# Xe_VDK_Schematic_-_Copy.net
KiCad netlist of a schematic drawn in Altium Designer
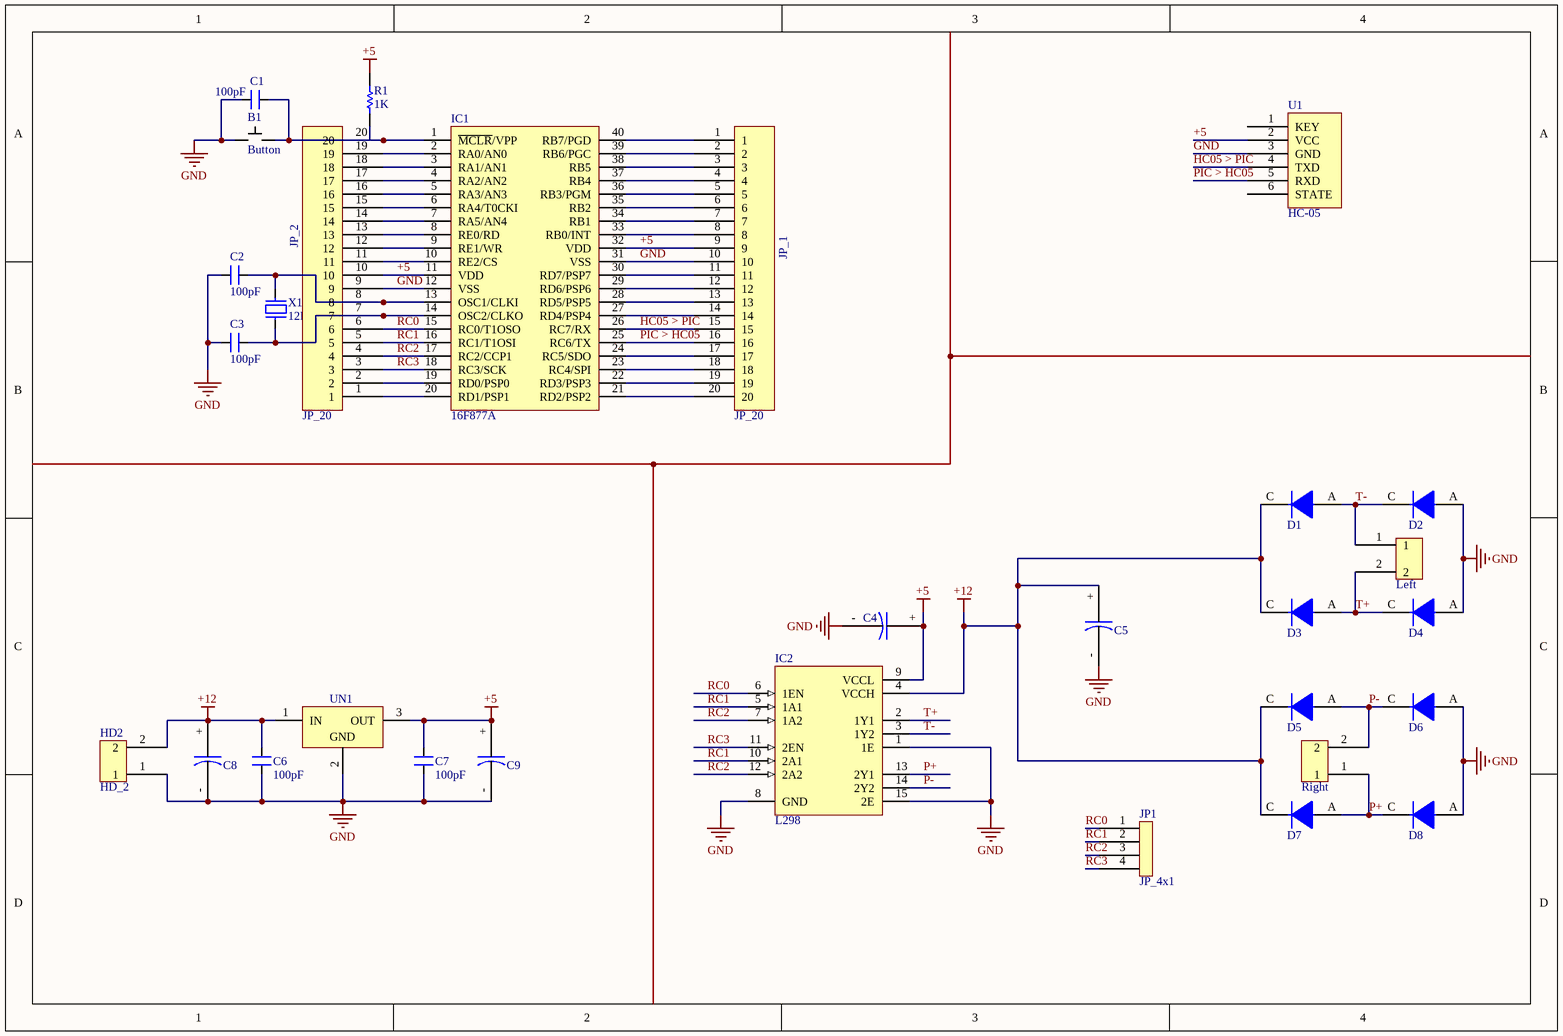
[diagram p0: Xe_VDK_Schematic - Copy.SchDoc]

(export (version "E")
  (design (tool "Eeschema 10.0.6"))
  (components
    (comp (ref "B1")
      (value "Button")
      (footprint "Button - 4-pin")
      (libsource (lib "LuongTanDat") (part "Button"))
    )
    (comp (ref "C1")
      (value "100pF")
      (footprint "CN1")
      (description "Cap np  1pF - 472pF")
      (libsource (lib "syhaunguyen") (part "CN1"))
    )
    (comp (ref "C2")
      (value "100pF")
      (footprint "CN1")
      (description "Cap np  1pF - 472pF")
      (libsource (lib "syhaunguyen") (part "CN1"))
    )
    (comp (ref "C3")
      (value "100pF")
      (footprint "CN1")
      (description "Cap np  1pF - 472pF")
      (libsource (lib "syhaunguyen") (part "CN1"))
    )
    (comp (ref "C4")
      (value "Pol-Cap")
      (footprint "Pol_200mil")
      (description "Tụ điện phân cực")
      (libsource (lib "LuongTanDat") (part "Pol-Cap"))
    )
    (comp (ref "C5")
      (value "Pol-Cap")
      (footprint "Pol_200mil")
      (description "Tụ điện phân cực")
      (libsource (lib "LuongTanDat") (part "Pol-Cap"))
    )
    (comp (ref "C6")
      (value "100pF")
      (footprint "CN1")
      (description "Cap np  1pF - 472pF")
      (libsource (lib "syhaunguyen") (part "CN1"))
    )
    (comp (ref "C7")
      (value "100pF")
      (footprint "CN1")
      (description "Cap np  1pF - 472pF")
      (libsource (lib "syhaunguyen") (part "CN1"))
    )
    (comp (ref "C8")
      (value "Pol-Cap")
      (footprint "POL_250mil")
      (description "Tụ điện phân cực")
      (libsource (lib "LuongTanDat") (part "Pol-Cap"))
    )
    (comp (ref "C9")
      (value "Pol-Cap")
      (footprint "POL_250mil")
      (description "Tụ điện phân cực")
      (libsource (lib "LuongTanDat") (part "Pol-Cap"))
    )
    (comp (ref "D1") (value "Diode") (footprint "Diode") (libsource (lib "LuongTanDat") (part "Diode")))
    (comp (ref "D2") (value "Diode") (footprint "Diode") (libsource (lib "LuongTanDat") (part "Diode")))
    (comp (ref "D3") (value "Diode") (footprint "Diode") (libsource (lib "LuongTanDat") (part "Diode")))
    (comp (ref "D4") (value "Diode") (footprint "Diode") (libsource (lib "LuongTanDat") (part "Diode")))
    (comp (ref "D5") (value "Diode") (footprint "Diode") (libsource (lib "LuongTanDat") (part "Diode")))
    (comp (ref "D6") (value "Diode") (footprint "Diode") (libsource (lib "LuongTanDat") (part "Diode")))
    (comp (ref "D7") (value "Diode") (footprint "Diode") (libsource (lib "LuongTanDat") (part "Diode")))
    (comp (ref "D8") (value "Diode") (footprint "Diode") (libsource (lib "LuongTanDat") (part "Diode")))
    (comp (ref "HD2") (value "HD_2") (footprint "Header 2") (libsource (lib "LuongTanDat") (part "HD_2")))
    (comp (ref "IC1")
      (value "16F877A")
      (footprint "DIP40/W0.6")
      (description "8K FLASH, 368B RAM, 256B EFROM")
      (fields (field (name "COPYRIGHT BY") "VanDungEvn"))
      (libsource (lib "syhaunguyen") (part "16F877"))
    )
    (comp (ref "IC2")
      (value "L298")
      (footprint "DIP15SL2")
      (description "Dual Full-H Driver")
      (fields (field (name "PUBLISHER") "Altium Limited"))
      (libsource (lib "VioletofSun") (part "L298"))
    )
    (comp (ref "JP1") (value "JP_4x1") (footprint "JP_4x1") (libsource (lib "LuongTanDat") (part "JP_4x1")))
    (comp (ref "JP_1") (value "JP_20") (footprint "JP_20") (libsource (lib "LuongTanDat") (part "JP_20")))
    (comp (ref "JP_2") (value "JP_20") (footprint "JP_20") (libsource (lib "") (part "JP_20_1")))
    (comp (ref "Left") (value "HD_2") (footprint "Header 2") (libsource (lib "") (part "HD_2_1")))
    (comp (ref "R1")
      (value "1K")
      (footprint "RES 1/2W")
      (description "Resistor")
      (fields (field (name "Comment") "RESISTOR"))
      (libsource (lib "PIF_Library") (part "RESISTOR"))
    )
    (comp (ref "Right") (value "HD_2") (footprint "Header 2") (libsource (lib "LuongTanDat") (part "HD_2")))
    (comp (ref "U1") (value "HC-05") (footprint "HC-05") (libsource (lib "LuongTanDat") (part "HC-05")))
    (comp (ref "UN1")
      (value "LM7805")
      (footprint "QTO-220")
      (description "Positive Voltage Regulator")
      (libsource (lib "PIF_Library") (part "LM7805"))
    )
    (comp (ref "X1")
      (value "12Mhz")
      (footprint "XT2")
      (description "Crystal, 32.768 KHz, -40 to 85 degC, 3.2 x 1.5 x 0.9 mm SMD")
      (libsource (lib "ImetAltiumLibrary") (part "XT2"))
    )
  )
  (nets
    (net (code "1") (name "+5") (class "Default")
      (node (ref "C4") (pin "+") (pintype "passive"))
      (node (ref "C7") (pin "2") (pinfunction "2_2") (pintype "passive"))
      (node (ref "C9") (pin "+") (pintype "passive"))
      (node (ref "IC1") (pin "11") (pinfunction "VDD_11") (pintype "passive"))
      (node (ref "IC1") (pin "32") (pinfunction "VDD_32") (pintype "passive"))
      (node (ref "IC2") (pin "9") (pinfunction "VCCL_9") (pintype "power_in"))
      (node (ref "JP_1") (pin "9") (pinfunction "9_9") (pintype "passive"))
      (node (ref "JP_2") (pin "10") (pinfunction "10_10") (pintype "passive"))
      (node (ref "R1") (pin "2") (pinfunction "2_2") (pintype "passive"))
      (node (ref "U1") (pin "2") (pinfunction "VCC_2") (pintype "passive"))
      (node (ref "UN1") (pin "3") (pinfunction "OUT_3") (pintype "power_in"))
    )
    (net (code "2") (name "+12") (class "Default")
      (node (ref "C5") (pin "+") (pintype "passive"))
      (node (ref "C6") (pin "2") (pinfunction "2_2") (pintype "passive"))
      (node (ref "C8") (pin "+") (pintype "passive"))
      (node (ref "D1") (pin "C") (pinfunction "2_C") (pintype "passive"))
      (node (ref "D3") (pin "C") (pinfunction "2_C") (pintype "passive"))
      (node (ref "D5") (pin "C") (pinfunction "2_C") (pintype "passive"))
      (node (ref "D7") (pin "C") (pinfunction "2_C") (pintype "passive"))
      (node (ref "HD2") (pin "2") (pinfunction "2_2") (pintype "passive"))
      (node (ref "IC2") (pin "4") (pinfunction "VCCH_4") (pintype "power_in"))
      (node (ref "UN1") (pin "1") (pinfunction "IN_1") (pintype "power_in"))
    )
    (net (code "3") (name "/HC05 > PIC") (class "Default")
      (node (ref "IC1") (pin "26") (pinfunction "RC7/RX_26") (pintype "passive"))
      (node (ref "JP_1") (pin "15") (pinfunction "15_15") (pintype "passive"))
      (node (ref "U1") (pin "4") (pinfunction "TXD_4") (pintype "passive"))
    )
    (net (code "4") (name "/P+") (class "Default")
      (node (ref "D7") (pin "A") (pinfunction "1_A") (pintype "passive"))
      (node (ref "D8") (pin "C") (pinfunction "2_C") (pintype "passive"))
      (node (ref "IC2") (pin "13") (pinfunction "2Y1_13") (pintype "tri_state"))
      (node (ref "Right") (pin "1") (pinfunction "1_1") (pintype "passive"))
    )
    (net (code "5") (name "/P-") (class "Default")
      (node (ref "D5") (pin "A") (pinfunction "1_A") (pintype "passive"))
      (node (ref "D6") (pin "C") (pinfunction "2_C") (pintype "passive"))
      (node (ref "IC2") (pin "14") (pinfunction "2Y2_14") (pintype "tri_state"))
      (node (ref "Right") (pin "2") (pinfunction "2_2") (pintype "passive"))
    )
    (net (code "6") (name "/PIC > HC05") (class "Default")
      (node (ref "IC1") (pin "25") (pinfunction "RC6/TX_25") (pintype "passive"))
      (node (ref "JP_1") (pin "16") (pinfunction "16_16") (pintype "passive"))
      (node (ref "U1") (pin "5") (pinfunction "RXD_5") (pintype "passive"))
    )
    (net (code "7") (name "/RC0") (class "Default")
      (node (ref "IC1") (pin "15") (pinfunction "RC0/T1OSO_15") (pintype "passive"))
      (node (ref "IC2") (pin "6") (pinfunction "1EN_6") (pintype "input"))
      (node (ref "JP1") (pin "1") (pinfunction "1_1") (pintype "passive"))
      (node (ref "JP_2") (pin "6") (pinfunction "6_6") (pintype "passive"))
    )
    (net (code "8") (name "/RC1") (class "Default")
      (node (ref "IC1") (pin "16") (pinfunction "RC1/T1OSI_16") (pintype "passive"))
      (node (ref "IC2") (pin "10") (pinfunction "2A1_10") (pintype "input"))
      (node (ref "IC2") (pin "5") (pinfunction "1A1_5") (pintype "input"))
      (node (ref "JP1") (pin "2") (pinfunction "2_2") (pintype "passive"))
      (node (ref "JP_2") (pin "5") (pinfunction "5_5") (pintype "passive"))
    )
    (net (code "9") (name "/RC2") (class "Default")
      (node (ref "IC1") (pin "17") (pinfunction "RC2/CCP1_17") (pintype "passive"))
      (node (ref "IC2") (pin "12") (pinfunction "2A2_12") (pintype "input"))
      (node (ref "IC2") (pin "7") (pinfunction "1A2_7") (pintype "input"))
      (node (ref "JP1") (pin "3") (pinfunction "3_3") (pintype "passive"))
      (node (ref "JP_2") (pin "4") (pinfunction "4_4") (pintype "passive"))
    )
    (net (code "10") (name "/RC3") (class "Default")
      (node (ref "IC1") (pin "18") (pinfunction "RC3/SCK_18") (pintype "passive"))
      (node (ref "IC2") (pin "11") (pinfunction "2EN_11") (pintype "input"))
      (node (ref "JP1") (pin "4") (pinfunction "4_4") (pintype "passive"))
      (node (ref "JP_2") (pin "3") (pinfunction "3_3") (pintype "passive"))
    )
    (net (code "11") (name "/T+") (class "Default")
      (node (ref "D3") (pin "A") (pinfunction "1_A") (pintype "passive"))
      (node (ref "D4") (pin "C") (pinfunction "2_C") (pintype "passive"))
      (node (ref "IC2") (pin "2") (pinfunction "1Y1_2") (pintype "tri_state"))
      (node (ref "Left") (pin "2") (pinfunction "2_2") (pintype "passive"))
    )
    (net (code "12") (name "/T-") (class "Default")
      (node (ref "D1") (pin "A") (pinfunction "1_A") (pintype "passive"))
      (node (ref "D2") (pin "C") (pinfunction "2_C") (pintype "passive"))
      (node (ref "IC2") (pin "3") (pinfunction "1Y2_3") (pintype "tri_state"))
      (node (ref "Left") (pin "1") (pinfunction "1_1") (pintype "passive"))
    )
    (net (code "13") (name "GND") (class "Default")
      (node (ref "B1") (pin "1") (pinfunction "0_1") (pintype "passive"))
      (node (ref "C1") (pin "1") (pinfunction "1_1") (pintype "passive"))
      (node (ref "C2") (pin "1") (pinfunction "1_1") (pintype "passive"))
      (node (ref "C3") (pin "1") (pinfunction "1_1") (pintype "passive"))
      (node (ref "C4") (pin "-") (pintype "passive"))
      (node (ref "C5") (pin "-") (pintype "passive"))
      (node (ref "C6") (pin "1") (pinfunction "1_1") (pintype "passive"))
      (node (ref "C7") (pin "1") (pinfunction "1_1") (pintype "passive"))
      (node (ref "C8") (pin "-") (pintype "passive"))
      (node (ref "C9") (pin "-") (pintype "passive"))
      (node (ref "D2") (pin "A") (pinfunction "1_A") (pintype "passive"))
      (node (ref "D4") (pin "A") (pinfunction "1_A") (pintype "passive"))
      (node (ref "D6") (pin "A") (pinfunction "1_A") (pintype "passive"))
      (node (ref "D8") (pin "A") (pinfunction "1_A") (pintype "passive"))
      (node (ref "HD2") (pin "1") (pinfunction "1_1") (pintype "passive"))
      (node (ref "IC1") (pin "12") (pinfunction "VSS_12") (pintype "passive"))
      (node (ref "IC1") (pin "31") (pinfunction "VSS_31") (pintype "passive"))
      (node (ref "IC2") (pin "1") (pinfunction "1E_1") (pintype "passive"))
      (node (ref "IC2") (pin "15") (pinfunction "2E_15") (pintype "passive"))
      (node (ref "IC2") (pin "8") (pinfunction "GND_8") (pintype "power_in"))
      (node (ref "JP_1") (pin "10") (pinfunction "10_10") (pintype "passive"))
      (node (ref "JP_2") (pin "9") (pinfunction "9_9") (pintype "passive"))
      (node (ref "U1") (pin "3") (pinfunction "GND_3") (pintype "passive"))
      (node (ref "UN1") (pin "2") (pinfunction "GND_2") (pintype "power_in"))
    )
    (net (code "14") (name "Net-(B1-10)") (class "Default")
      (node (ref "B1") (pin "2") (pinfunction "10_2") (pintype "passive"))
      (node (ref "C1") (pin "2") (pinfunction "2_2") (pintype "passive"))
      (node (ref "IC1") (pin "1") (pinfunction "~{MCLR}/VPP_1") (pintype "passive"))
      (node (ref "JP_2") (pin "20") (pinfunction "20_20") (pintype "passive"))
      (node (ref "R1") (pin "1") (pinfunction "1_1") (pintype "passive"))
    )
    (net (code "15") (name "Net-(IC1-OSC1{slash}CLKI)") (class "Default")
      (node (ref "C2") (pin "2") (pinfunction "2_2") (pintype "passive"))
      (node (ref "IC1") (pin "13") (pinfunction "OSC1/CLKI_13") (pintype "passive"))
      (node (ref "JP_2") (pin "8") (pinfunction "8_8") (pintype "passive"))
      (node (ref "X1") (pin "2") (pinfunction "2_2") (pintype "passive"))
    )
    (net (code "16") (name "Net-(IC1-OSC2{slash}CLKO)") (class "Default")
      (node (ref "C3") (pin "2") (pinfunction "2_2") (pintype "passive"))
      (node (ref "IC1") (pin "14") (pinfunction "OSC2/CLKO_14") (pintype "passive"))
      (node (ref "JP_2") (pin "7") (pinfunction "7_7") (pintype "passive"))
      (node (ref "X1") (pin "1") (pinfunction "1_1") (pintype "passive"))
    )
    (net (code "17") (name "Net-(IC1-RA0{slash}AN0)") (class "Default")
      (node (ref "IC1") (pin "2") (pinfunction "RA0/AN0_2") (pintype "passive"))
      (node (ref "JP_2") (pin "19") (pinfunction "19_19") (pintype "passive"))
    )
    (net (code "18") (name "Net-(IC1-RA1{slash}AN1)") (class "Default")
      (node (ref "IC1") (pin "3") (pinfunction "RA1/AN1_3") (pintype "passive"))
      (node (ref "JP_2") (pin "18") (pinfunction "18_18") (pintype "passive"))
    )
    (net (code "19") (name "Net-(IC1-RA2{slash}AN2)") (class "Default")
      (node (ref "IC1") (pin "4") (pinfunction "RA2/AN2_4") (pintype "passive"))
      (node (ref "JP_2") (pin "17") (pinfunction "17_17") (pintype "passive"))
    )
    (net (code "20") (name "Net-(IC1-RA3{slash}AN3)") (class "Default")
      (node (ref "IC1") (pin "5") (pinfunction "RA3/AN3_5") (pintype "passive"))
      (node (ref "JP_2") (pin "16") (pinfunction "16_16") (pintype "passive"))
    )
    (net (code "21") (name "Net-(IC1-RA4{slash}T0CKI)") (class "Default")
      (node (ref "IC1") (pin "6") (pinfunction "RA4/T0CKI_6") (pintype "passive"))
      (node (ref "JP_2") (pin "15") (pinfunction "15_15") (pintype "passive"))
    )
    (net (code "22") (name "Net-(IC1-RA5{slash}AN4)") (class "Default")
      (node (ref "IC1") (pin "7") (pinfunction "RA5/AN4_7") (pintype "passive"))
      (node (ref "JP_2") (pin "14") (pinfunction "14_14") (pintype "passive"))
    )
    (net (code "23") (name "Net-(IC1-RB0{slash}INT)") (class "Default")
      (node (ref "IC1") (pin "33") (pinfunction "RB0/INT_33") (pintype "passive"))
      (node (ref "JP_1") (pin "8") (pinfunction "8_8") (pintype "passive"))
    )
    (net (code "24") (name "Net-(IC1-RB1)") (class "Default")
      (node (ref "IC1") (pin "34") (pinfunction "RB1_34") (pintype "passive"))
      (node (ref "JP_1") (pin "7") (pinfunction "7_7") (pintype "passive"))
    )
    (net (code "25") (name "Net-(IC1-RB2)") (class "Default")
      (node (ref "IC1") (pin "35") (pinfunction "RB2_35") (pintype "passive"))
      (node (ref "JP_1") (pin "6") (pinfunction "6_6") (pintype "passive"))
    )
    (net (code "26") (name "Net-(IC1-RB3{slash}PGM)") (class "Default")
      (node (ref "IC1") (pin "36") (pinfunction "RB3/PGM_36") (pintype "passive"))
      (node (ref "JP_1") (pin "5") (pinfunction "5_5") (pintype "passive"))
    )
    (net (code "27") (name "Net-(IC1-RB4)") (class "Default")
      (node (ref "IC1") (pin "37") (pinfunction "RB4_37") (pintype "passive"))
      (node (ref "JP_1") (pin "4") (pinfunction "4_4") (pintype "passive"))
    )
    (net (code "28") (name "Net-(IC1-RB5)") (class "Default")
      (node (ref "IC1") (pin "38") (pinfunction "RB5_38") (pintype "passive"))
      (node (ref "JP_1") (pin "3") (pinfunction "3_3") (pintype "passive"))
    )
    (net (code "29") (name "Net-(IC1-RB6{slash}PGC)") (class "Default")
      (node (ref "IC1") (pin "39") (pinfunction "RB6/PGC_39") (pintype "passive"))
      (node (ref "JP_1") (pin "2") (pinfunction "2_2") (pintype "passive"))
    )
    (net (code "30") (name "Net-(IC1-RB7{slash}PGD)") (class "Default")
      (node (ref "IC1") (pin "40") (pinfunction "RB7/PGD_40") (pintype "passive"))
      (node (ref "JP_1") (pin "1") (pinfunction "1_1") (pintype "passive"))
    )
    (net (code "31") (name "Net-(IC1-RC4{slash}SPI)") (class "Default")
      (node (ref "IC1") (pin "23") (pinfunction "RC4/SPI_23") (pintype "passive"))
      (node (ref "JP_1") (pin "18") (pinfunction "18_18") (pintype "passive"))
    )
    (net (code "32") (name "Net-(IC1-RC5{slash}SDO)") (class "Default")
      (node (ref "IC1") (pin "24") (pinfunction "RC5/SDO_24") (pintype "passive"))
      (node (ref "JP_1") (pin "17") (pinfunction "17_17") (pintype "passive"))
    )
    (net (code "33") (name "Net-(IC1-RD0{slash}PSP0)") (class "Default")
      (node (ref "IC1") (pin "19") (pinfunction "RD0/PSP0_19") (pintype "passive"))
      (node (ref "JP_2") (pin "2") (pinfunction "2_2") (pintype "passive"))
    )
    (net (code "34") (name "Net-(IC1-RD1{slash}PSP1)") (class "Default")
      (node (ref "IC1") (pin "20") (pinfunction "RD1/PSP1_20") (pintype "passive"))
      (node (ref "JP_2") (pin "1") (pinfunction "1_1") (pintype "passive"))
    )
    (net (code "35") (name "Net-(IC1-RD2{slash}PSP2)") (class "Default")
      (node (ref "IC1") (pin "21") (pinfunction "RD2/PSP2_21") (pintype "passive"))
      (node (ref "JP_1") (pin "20") (pinfunction "20_20") (pintype "passive"))
    )
    (net (code "36") (name "Net-(IC1-RD3{slash}PSP3)") (class "Default")
      (node (ref "IC1") (pin "22") (pinfunction "RD3/PSP3_22") (pintype "passive"))
      (node (ref "JP_1") (pin "19") (pinfunction "19_19") (pintype "passive"))
    )
    (net (code "37") (name "Net-(IC1-RD4{slash}PSP4)") (class "Default")
      (node (ref "IC1") (pin "27") (pinfunction "RD4/PSP4_27") (pintype "passive"))
      (node (ref "JP_1") (pin "14") (pinfunction "14_14") (pintype "passive"))
    )
    (net (code "38") (name "Net-(IC1-RD5{slash}PSP5)") (class "Default")
      (node (ref "IC1") (pin "28") (pinfunction "RD5/PSP5_28") (pintype "passive"))
      (node (ref "JP_1") (pin "13") (pinfunction "13_13") (pintype "passive"))
    )
    (net (code "39") (name "Net-(IC1-RD6{slash}PSP6)") (class "Default")
      (node (ref "IC1") (pin "29") (pinfunction "RD6/PSP6_29") (pintype "passive"))
      (node (ref "JP_1") (pin "12") (pinfunction "12_12") (pintype "passive"))
    )
    (net (code "40") (name "Net-(IC1-RD7{slash}PSP7)") (class "Default")
      (node (ref "IC1") (pin "30") (pinfunction "RD7/PSP7_30") (pintype "passive"))
      (node (ref "JP_1") (pin "11") (pinfunction "11_11") (pintype "passive"))
    )
    (net (code "41") (name "Net-(IC1-RE0{slash}RD)") (class "Default")
      (node (ref "IC1") (pin "8") (pinfunction "RE0/RD_8") (pintype "passive"))
      (node (ref "JP_2") (pin "13") (pinfunction "13_13") (pintype "passive"))
    )
    (net (code "42") (name "Net-(IC1-RE1{slash}WR)") (class "Default")
      (node (ref "IC1") (pin "9") (pinfunction "RE1/WR_9") (pintype "passive"))
      (node (ref "JP_2") (pin "12") (pinfunction "12_12") (pintype "passive"))
    )
    (net (code "43") (name "Net-(IC1-RE2{slash}CS)") (class "Default")
      (node (ref "IC1") (pin "10") (pinfunction "RE2/CS_10") (pintype "passive"))
      (node (ref "JP_2") (pin "11") (pinfunction "11_11") (pintype "passive"))
    )
    (net (code "44") (name "unconnected-(U1-KEY-Pad1)") (class "Default")
      (node (ref "U1") (pin "1") (pinfunction "KEY_1") (pintype "passive"))
    )
    (net (code "45") (name "unconnected-(U1-STATE-Pad6)") (class "Default")
      (node (ref "U1") (pin "6") (pinfunction "STATE_6") (pintype "passive"))
    )
  )
)
